# PROC054D_Host_Connector.net
KiCad netlist of a schematic drawn in Altium Designer
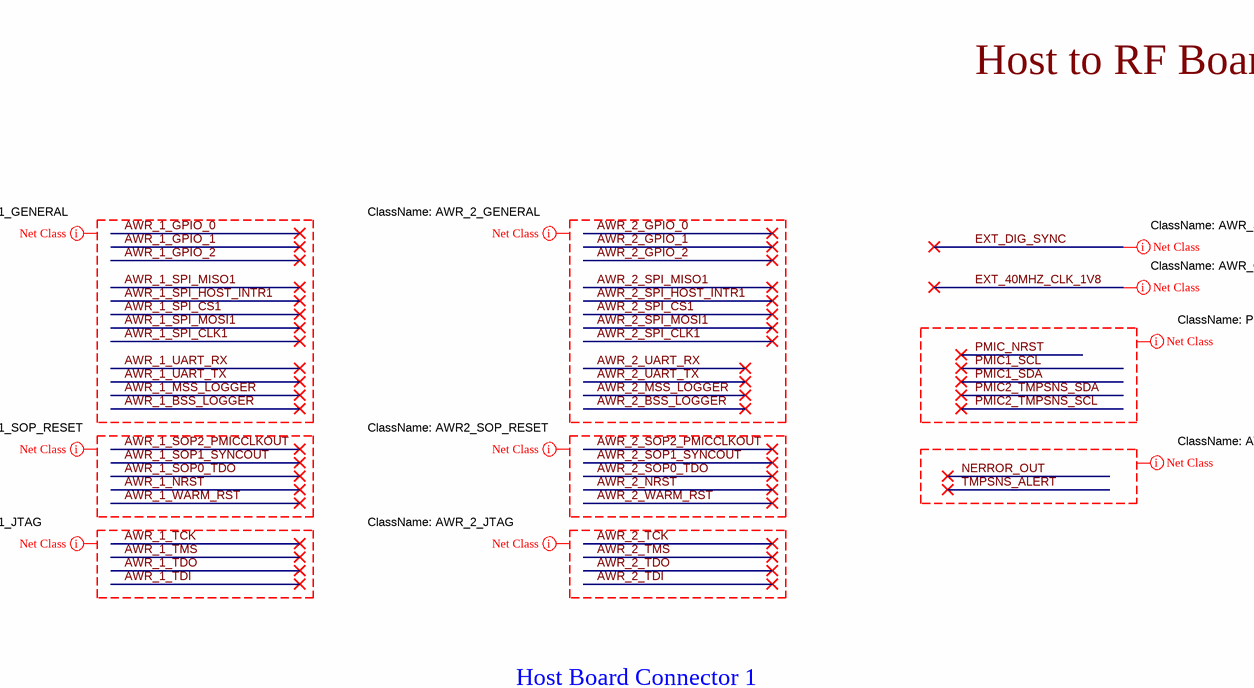
[diagram p0: PROC054D_Host_Connector.SchDoc, top left]
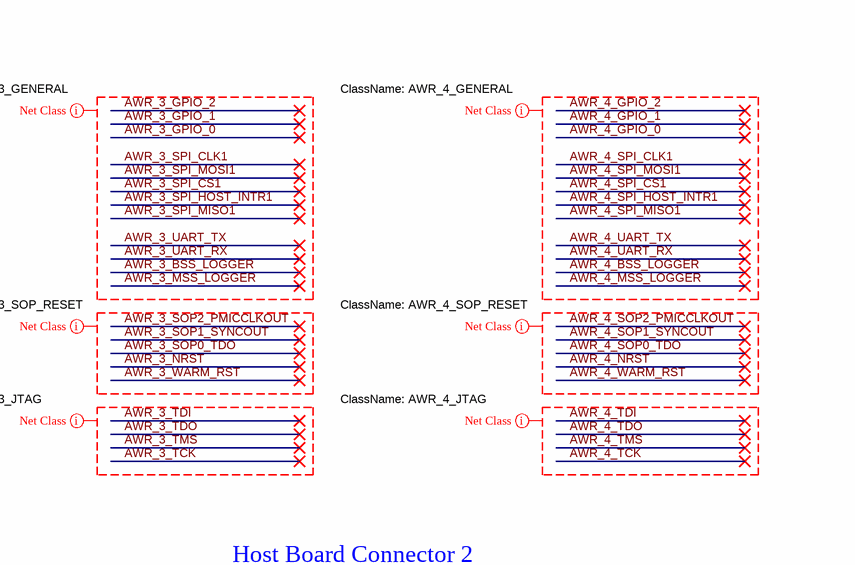
[diagram p1: PROC054D_Host_Connector.SchDoc, top right]
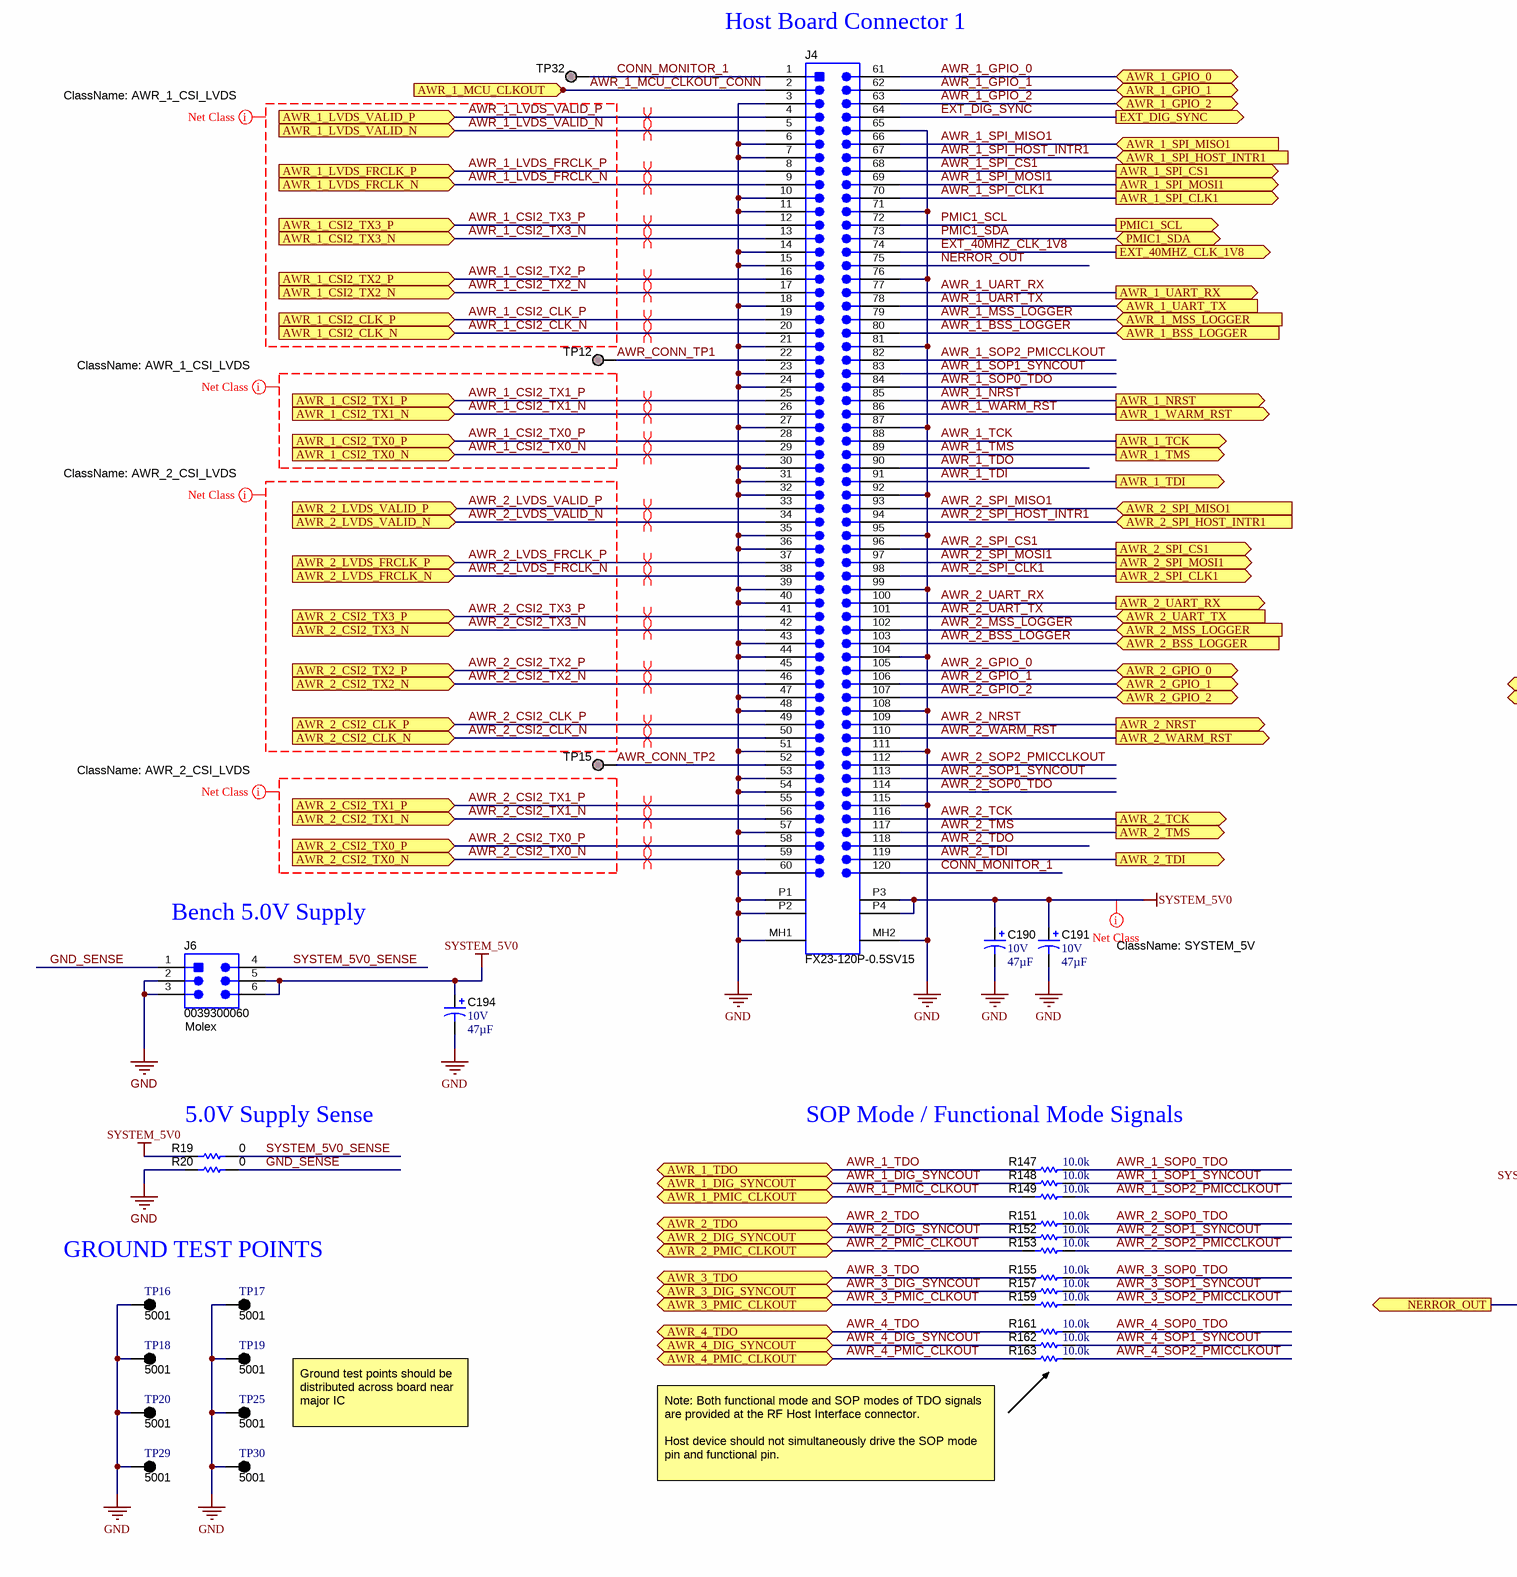
[diagram p2: PROC054D_Host_Connector.SchDoc, bottom left]
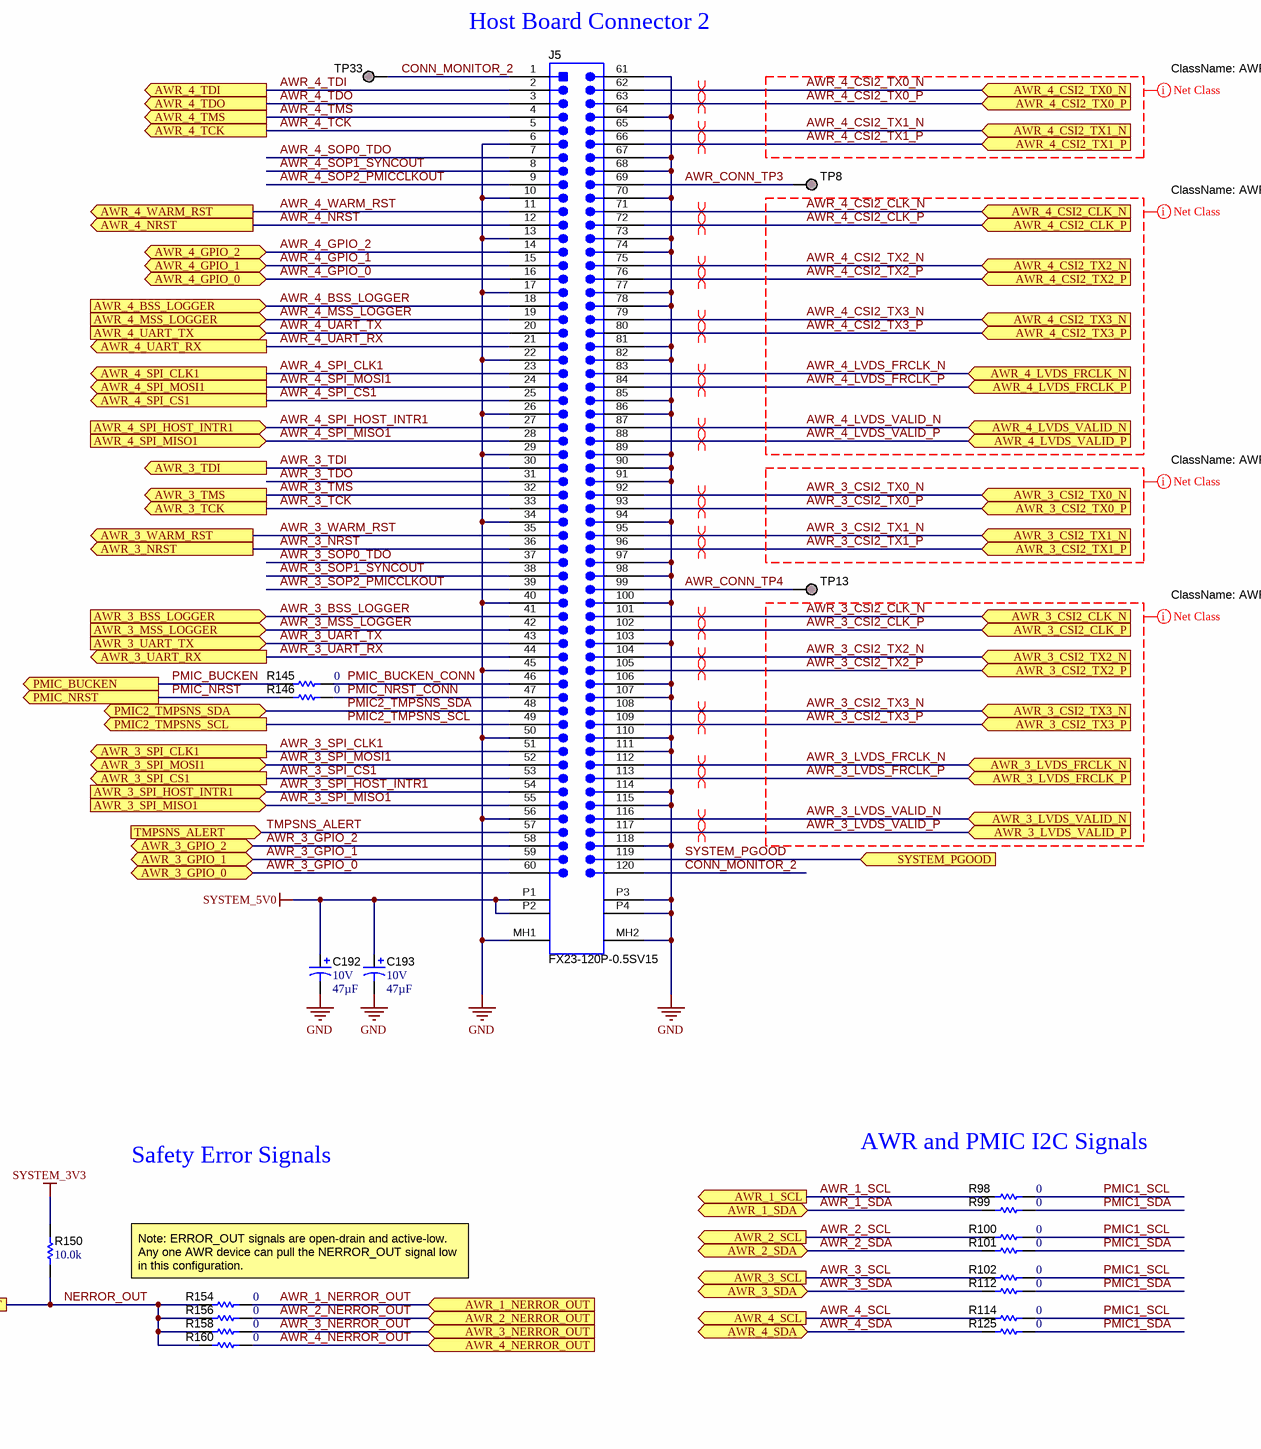
[diagram p3: PROC054D_Host_Connector.SchDoc, bottom right]

(export (version "E")
  (design (tool "Eeschema 10.0.6"))
  (components
    (comp (ref "C190")
      (value "T491B476K010AT")
      (footprint "3528-21")
      (description "CAP, TA, 47 µF, 10 V, +/- 10%, SMD")
      (fields
        (field (name "MANUFACTURER") "Kemet")
        (field (name "VDC_V") "10V")
        (field (name "VALUEDISPLAYED") "47µF")
      )
      (libsource (lib "Altium Vault - TI") (part "CMP-0078216-1"))
    )
    (comp (ref "C191")
      (value "T491B476K010AT")
      (footprint "3528-21")
      (description "CAP, TA, 47 µF, 10 V, +/- 10%, SMD")
      (fields
        (field (name "MANUFACTURER") "Kemet")
        (field (name "VDC_V") "10V")
        (field (name "VALUEDISPLAYED") "47µF")
      )
      (libsource (lib "Altium Vault - TI") (part "Cap_Polarized"))
    )
    (comp (ref "C192")
      (value "T491B476K010AT")
      (footprint "3528-21")
      (description "CAP, TA, 47 µF, 10 V, +/- 10%, SMD")
      (fields
        (field (name "MANUFACTURER") "Kemet")
        (field (name "VDC_V") "10V")
        (field (name "VALUEDISPLAYED") "47µF")
      )
      (libsource (lib "Altium Vault - TI") (part "Cap_Polarized"))
    )
    (comp (ref "C193")
      (value "T491B476K010AT")
      (footprint "3528-21")
      (description "CAP, TA, 47 µF, 10 V, +/- 10%, SMD")
      (fields
        (field (name "MANUFACTURER") "Kemet")
        (field (name "VDC_V") "10V")
        (field (name "VALUEDISPLAYED") "47µF")
      )
      (libsource (lib "Altium Vault - TI") (part "Cap_Polarized"))
    )
    (comp (ref "C194")
      (value "T491B476K010AT")
      (footprint "3528-21")
      (description "CAP, TA, 47 µF, 10 V, +/- 10%, SMD")
      (fields
        (field (name "MANUFACTURER") "Kemet")
        (field (name "VDC_V") "10V")
        (field (name "VALUEDISPLAYED") "47µF")
      )
      (libsource (lib "Altium Vault - TI") (part "CMP-0078216-1"))
    )
    (comp (ref "J4")
      (value "FX23-120P-0.5SV15")
      (footprint "Hirose_FX23-120P-0_5SV15")
      (description "Header(shrouded), 0.5mm, 60x2, Gold, SMT")
      (fields (field (name "MANUFACTURER") "Hirose Electric Co. Ltd."))
      (libsource (lib "Altium Vault - TI") (part "Hirose_FX23-120P-0_5SV15"))
    )
    (comp (ref "J5")
      (value "FX23-120P-0.5SV15")
      (footprint "Hirose_FX23-120P-0_5SV15")
      (description "Header(shrouded), 0.5mm, 60x2, Gold, SMT")
      (fields (field (name "MANUFACTURER") "Hirose Electric Co. Ltd."))
      (libsource (lib "Altium Vault - TI") (part "Hirose_FX23-120P-0_5SV15"))
    )
    (comp (ref "J6")
      (value "0039300060")
      (footprint "Molex_0039300060")
      (description "Header(shrouded), 4.2mm, 3x2, Tin, R/A, TH")
      (fields (field (name "MANUFACTURER") "Molex"))
      (libsource (lib "Altium Vault - TI") (part "CMP-0082107-1"))
    )
    (comp (ref "R19")
      (value "PMR10EZPJ000")
      (footprint "0805L")
      (description "RES, 0, 0%,  W, AEC-Q200 Grade 0, 0805")
      (fields (field (name "MANUFACTURER") "Rohm") (field (name "VALUEDISPLAYED") "0"))
      (libsource (lib "Altium Vault - TI") (part "CMP-0081857-1"))
    )
    (comp (ref "R20")
      (value "PMR10EZPJ000")
      (footprint "0805L")
      (description "RES, 0, 0%,  W, AEC-Q200 Grade 0, 0805")
      (fields (field (name "MANUFACTURER") "Rohm") (field (name "VALUEDISPLAYED") "0"))
      (libsource (lib "Altium Vault - TI") (part "CMP-0081857-1"))
    )
    (comp (ref "R98")
      (value "CRCW04020000Z0EDHP")
      (footprint "0402S")
      (description "RES, 0, 0%, 0.2 W, AEC-Q200 Grade 0, 0402")
      (fields (field (name "MANUFACTURER") "Vishay-Dale") (field (name "VALUEDISPLAYED") "0"))
      (libsource (lib "Altium Vault - TI") (part "CMP-0081856-1"))
    )
    (comp (ref "R99")
      (value "CRCW04020000Z0EDHP")
      (footprint "0402S")
      (description "RES, 0, 0%, 0.2 W, AEC-Q200 Grade 0, 0402")
      (fields (field (name "MANUFACTURER") "Vishay-Dale") (field (name "VALUEDISPLAYED") "0"))
      (libsource (lib "Altium Vault - TI") (part "CMP-0081856-1"))
    )
    (comp (ref "R100")
      (value "CRCW04020000Z0EDHP")
      (footprint "0402S")
      (description "RES, 0, 0%, 0.2 W, AEC-Q200 Grade 0, 0402")
      (fields (field (name "MANUFACTURER") "Vishay-Dale") (field (name "VALUEDISPLAYED") "0"))
      (libsource (lib "Altium Vault - TI") (part "CMP-0081856-1"))
    )
    (comp (ref "R101")
      (value "CRCW04020000Z0EDHP")
      (footprint "0402S")
      (description "RES, 0, 0%, 0.2 W, AEC-Q200 Grade 0, 0402")
      (fields (field (name "MANUFACTURER") "Vishay-Dale") (field (name "VALUEDISPLAYED") "0"))
      (libsource (lib "Altium Vault - TI") (part "CMP-0081856-1"))
    )
    (comp (ref "R102")
      (value "CRCW04020000Z0EDHP")
      (footprint "0402S")
      (description "RES, 0, 0%, 0.2 W, AEC-Q200 Grade 0, 0402")
      (fields (field (name "MANUFACTURER") "Vishay-Dale") (field (name "VALUEDISPLAYED") "0"))
      (libsource (lib "Altium Vault - TI") (part "CMP-0081856-1"))
    )
    (comp (ref "R112")
      (value "CRCW04020000Z0EDHP")
      (footprint "0402S")
      (description "RES, 0, 0%, 0.2 W, AEC-Q200 Grade 0, 0402")
      (fields (field (name "MANUFACTURER") "Vishay-Dale") (field (name "VALUEDISPLAYED") "0"))
      (libsource (lib "Altium Vault - TI") (part "CMP-0081856-1"))
    )
    (comp (ref "R114")
      (value "CRCW04020000Z0EDHP")
      (footprint "0402S")
      (description "RES, 0, 0%, 0.2 W, AEC-Q200 Grade 0, 0402")
      (fields (field (name "MANUFACTURER") "Vishay-Dale") (field (name "VALUEDISPLAYED") "0"))
      (libsource (lib "Altium Vault - TI") (part "CMP-0081856-1"))
    )
    (comp (ref "R125")
      (value "CRCW04020000Z0EDHP")
      (footprint "0402S")
      (description "RES, 0, 0%, 0.2 W, AEC-Q200 Grade 0, 0402")
      (fields (field (name "MANUFACTURER") "Vishay-Dale") (field (name "VALUEDISPLAYED") "0"))
      (libsource (lib "Altium Vault - TI") (part "CMP-0081856-1"))
    )
    (comp (ref "R145")
      (value "ERJ-2GE0R00X")
      (footprint "0402")
      (description "RES, 0, 5%, 0.1 W, AEC-Q200 Grade 0, 0402")
      (fields (field (name "MANUFACTURER") "Panasonic") (field (name "VALUEDISPLAYED") "0"))
      (libsource (lib "Altium Vault - TI") (part "Resistor"))
    )
    (comp (ref "R146")
      (value "ERJ-2GE0R00X")
      (footprint "0402")
      (description "RES, 0, 5%, 0.1 W, AEC-Q200 Grade 0, 0402")
      (fields (field (name "MANUFACTURER") "Panasonic") (field (name "VALUEDISPLAYED") "0"))
      (libsource (lib "Altium Vault - TI") (part "Resistor"))
    )
    (comp (ref "R147")
      (value "CRCW040210K0FKED")
      (footprint "0402")
      (description "RES, 10.0 k, 1%, 0.063 W, AEC-Q200 Grade 0, 0402")
      (fields (field (name "MANUFACTURER") "Vishay-Dale") (field (name "VALUEDISPLAYED") "10.0k"))
      (libsource (lib "Altium Vault - TI") (part "Resistor"))
    )
    (comp (ref "R148")
      (value "CRCW040210K0FKED")
      (footprint "0402")
      (description "RES, 10.0 k, 1%, 0.063 W, AEC-Q200 Grade 0, 0402")
      (fields (field (name "MANUFACTURER") "Vishay-Dale") (field (name "VALUEDISPLAYED") "10.0k"))
      (libsource (lib "Altium Vault - TI") (part "Resistor"))
    )
    (comp (ref "R149")
      (value "CRCW040210K0FKED")
      (footprint "0402")
      (description "RES, 10.0 k, 1%, 0.063 W, AEC-Q200 Grade 0, 0402")
      (fields (field (name "MANUFACTURER") "Vishay-Dale") (field (name "VALUEDISPLAYED") "10.0k"))
      (libsource (lib "Altium Vault - TI") (part "Resistor"))
    )
    (comp (ref "R150")
      (value "CRCW040210K0FKED")
      (footprint "0402")
      (description "RES, 10.0 k, 1%, 0.063 W, AEC-Q200 Grade 0, 0402")
      (fields (field (name "MANUFACTURER") "Vishay-Dale") (field (name "VALUEDISPLAYED") "10.0k"))
      (libsource (lib "Altium Vault - TI") (part "Resistor"))
    )
    (comp (ref "R151")
      (value "CRCW040210K0FKED")
      (footprint "0402")
      (description "RES, 10.0 k, 1%, 0.063 W, AEC-Q200 Grade 0, 0402")
      (fields (field (name "MANUFACTURER") "Vishay-Dale") (field (name "VALUEDISPLAYED") "10.0k"))
      (libsource (lib "Altium Vault - TI") (part "Resistor"))
    )
    (comp (ref "R152")
      (value "CRCW040210K0FKED")
      (footprint "0402")
      (description "RES, 10.0 k, 1%, 0.063 W, AEC-Q200 Grade 0, 0402")
      (fields (field (name "MANUFACTURER") "Vishay-Dale") (field (name "VALUEDISPLAYED") "10.0k"))
      (libsource (lib "Altium Vault - TI") (part "Resistor"))
    )
    (comp (ref "R153")
      (value "CRCW040210K0FKED")
      (footprint "0402")
      (description "RES, 10.0 k, 1%, 0.063 W, AEC-Q200 Grade 0, 0402")
      (fields (field (name "MANUFACTURER") "Vishay-Dale") (field (name "VALUEDISPLAYED") "10.0k"))
      (libsource (lib "Altium Vault - TI") (part "Resistor"))
    )
    (comp (ref "R154")
      (value "CRCW04020000Z0EDHP")
      (footprint "0402S")
      (description "RES, 0, 0%, 0.2 W, AEC-Q200 Grade 0, 0402")
      (fields (field (name "MANUFACTURER") "Vishay-Dale") (field (name "VALUEDISPLAYED") "0"))
      (libsource (lib "Altium Vault - TI") (part "CMP-0081856-1"))
    )
    (comp (ref "R155")
      (value "CRCW040210K0FKED")
      (footprint "0402")
      (description "RES, 10.0 k, 1%, 0.063 W, AEC-Q200 Grade 0, 0402")
      (fields (field (name "MANUFACTURER") "Vishay-Dale") (field (name "VALUEDISPLAYED") "10.0k"))
      (libsource (lib "Altium Vault - TI") (part "Resistor"))
    )
    (comp (ref "R156")
      (value "CRCW04020000Z0EDHP")
      (footprint "0402S")
      (description "RES, 0, 0%, 0.2 W, AEC-Q200 Grade 0, 0402")
      (fields (field (name "MANUFACTURER") "Vishay-Dale") (field (name "VALUEDISPLAYED") "0"))
      (libsource (lib "Altium Vault - TI") (part "CMP-0081856-1"))
    )
    (comp (ref "R157")
      (value "CRCW040210K0FKED")
      (footprint "0402")
      (description "RES, 10.0 k, 1%, 0.063 W, AEC-Q200 Grade 0, 0402")
      (fields (field (name "MANUFACTURER") "Vishay-Dale") (field (name "VALUEDISPLAYED") "10.0k"))
      (libsource (lib "Altium Vault - TI") (part "Resistor"))
    )
    (comp (ref "R158")
      (value "CRCW04020000Z0EDHP")
      (footprint "0402S")
      (description "RES, 0, 0%, 0.2 W, AEC-Q200 Grade 0, 0402")
      (fields (field (name "MANUFACTURER") "Vishay-Dale") (field (name "VALUEDISPLAYED") "0"))
      (libsource (lib "Altium Vault - TI") (part "CMP-0081856-1"))
    )
    (comp (ref "R159")
      (value "CRCW040210K0FKED")
      (footprint "0402")
      (description "RES, 10.0 k, 1%, 0.063 W, AEC-Q200 Grade 0, 0402")
      (fields (field (name "MANUFACTURER") "Vishay-Dale") (field (name "VALUEDISPLAYED") "10.0k"))
      (libsource (lib "Altium Vault - TI") (part "Resistor"))
    )
    (comp (ref "R160")
      (value "CRCW04020000Z0EDHP")
      (footprint "0402S")
      (description "RES, 0, 0%, 0.2 W, AEC-Q200 Grade 0, 0402")
      (fields (field (name "MANUFACTURER") "Vishay-Dale") (field (name "VALUEDISPLAYED") "0"))
      (libsource (lib "Altium Vault - TI") (part "CMP-0081856-1"))
    )
    (comp (ref "R161")
      (value "CRCW040210K0FKED")
      (footprint "0402")
      (description "RES, 10.0 k, 1%, 0.063 W, AEC-Q200 Grade 0, 0402")
      (fields (field (name "MANUFACTURER") "Vishay-Dale") (field (name "VALUEDISPLAYED") "10.0k"))
      (libsource (lib "Altium Vault - TI") (part "Resistor"))
    )
    (comp (ref "R162")
      (value "CRCW040210K0FKED")
      (footprint "0402")
      (description "RES, 10.0 k, 1%, 0.063 W, AEC-Q200 Grade 0, 0402")
      (fields (field (name "MANUFACTURER") "Vishay-Dale") (field (name "VALUEDISPLAYED") "10.0k"))
      (libsource (lib "Altium Vault - TI") (part "Resistor"))
    )
    (comp (ref "R163")
      (value "CRCW040210K0FKED")
      (footprint "0402")
      (description "RES, 10.0 k, 1%, 0.063 W, AEC-Q200 Grade 0, 0402")
      (fields (field (name "MANUFACTURER") "Vishay-Dale") (field (name "VALUEDISPLAYED") "10.0k"))
      (libsource (lib "Altium Vault - TI") (part "Resistor"))
    )
    (comp (ref "TP8")
      (value "TP_SM_1MM")
      (footprint "TP_SM_1MM")
      (description "1mm Test Point, SMT")
      (fields (field (name "MANUFACTURER") "Any") (field (name "PUBLISHER") "Texas Instruments"))
      (libsource (lib "Altium Vault - TI") (part "CMP-0003825-1"))
    )
    (comp (ref "TP12")
      (value "TP_SM_1MM")
      (footprint "TP_SM_1MM")
      (description "1mm Test Point, SMT")
      (fields (field (name "MANUFACTURER") "Any") (field (name "PUBLISHER") "Texas Instruments"))
      (libsource (lib "Altium Vault - TI") (part "CMP-0003825-1"))
    )
    (comp (ref "TP13")
      (value "TP_SM_1MM")
      (footprint "TP_SM_1MM")
      (description "1mm Test Point, SMT")
      (fields (field (name "MANUFACTURER") "Any") (field (name "PUBLISHER") "Texas Instruments"))
      (libsource (lib "Altium Vault - TI") (part "CMP-0003825-1"))
    )
    (comp (ref "TP15")
      (value "TP_SM_1MM")
      (footprint "TP_SM_1MM")
      (description "1mm Test Point, SMT")
      (fields (field (name "MANUFACTURER") "Any") (field (name "PUBLISHER") "Texas Instruments"))
      (libsource (lib "Altium Vault - TI") (part "CMP-0003825-1"))
    )
    (comp (ref "TP16")
      (value "5001")
      (footprint "Keystone5001")
      (description "Test Point, Miniature, Black, TH")
      (fields (field (name "MANUFACTURER") "Keystone") (field (name "PUBLISHER") "Texas Instruments"))
      (libsource (lib "Altium Vault - TI") (part "5001"))
    )
    (comp (ref "TP17")
      (value "5001")
      (footprint "Keystone5001")
      (description "Test Point, Miniature, Black, TH")
      (fields (field (name "MANUFACTURER") "Keystone") (field (name "PUBLISHER") "Texas Instruments"))
      (libsource (lib "Altium Vault - TI") (part "5001"))
    )
    (comp (ref "TP18")
      (value "5001")
      (footprint "Keystone5001")
      (description "Test Point, Miniature, Black, TH")
      (fields (field (name "MANUFACTURER") "Keystone") (field (name "PUBLISHER") "Texas Instruments"))
      (libsource (lib "Altium Vault - TI") (part "5001"))
    )
    (comp (ref "TP19")
      (value "5001")
      (footprint "Keystone5001")
      (description "Test Point, Miniature, Black, TH")
      (fields (field (name "MANUFACTURER") "Keystone") (field (name "PUBLISHER") "Texas Instruments"))
      (libsource (lib "Altium Vault - TI") (part "5001"))
    )
    (comp (ref "TP20")
      (value "5001")
      (footprint "Keystone5001")
      (description "Test Point, Miniature, Black, TH")
      (fields (field (name "MANUFACTURER") "Keystone") (field (name "PUBLISHER") "Texas Instruments"))
      (libsource (lib "Altium Vault - TI") (part "5001"))
    )
    (comp (ref "TP25")
      (value "5001")
      (footprint "Keystone5001")
      (description "Test Point, Miniature, Black, TH")
      (fields (field (name "MANUFACTURER") "Keystone") (field (name "PUBLISHER") "Texas Instruments"))
      (libsource (lib "Altium Vault - TI") (part "5001"))
    )
    (comp (ref "TP29")
      (value "5001")
      (footprint "Keystone5001")
      (description "Test Point, Miniature, Black, TH")
      (fields (field (name "MANUFACTURER") "Keystone") (field (name "PUBLISHER") "Texas Instruments"))
      (libsource (lib "Altium Vault - TI") (part "5001"))
    )
    (comp (ref "TP30")
      (value "5001")
      (footprint "Keystone5001")
      (description "Test Point, Miniature, Black, TH")
      (fields (field (name "MANUFACTURER") "Keystone") (field (name "PUBLISHER") "Texas Instruments"))
      (libsource (lib "Altium Vault - TI") (part "5001"))
    )
    (comp (ref "TP32")
      (value "TP_SM_1MM")
      (footprint "TP_SM_1MM")
      (description "1mm Test Point, SMT")
      (fields (field (name "MANUFACTURER") "Any") (field (name "PUBLISHER") "Texas Instruments"))
      (libsource (lib "Altium Vault - TI") (part "CMP-0003825-1"))
    )
    (comp (ref "TP33")
      (value "TP_SM_1MM")
      (footprint "TP_SM_1MM")
      (description "1mm Test Point, SMT")
      (fields (field (name "MANUFACTURER") "Any") (field (name "PUBLISHER") "Texas Instruments"))
      (libsource (lib "Altium Vault - TI") (part "CMP-0003825-1"))
    )
  )
  (nets
    (net (code "1") (name "/AWR_1_BSS_LOGGER") (class "Default")
      (node (ref "J4") (pin "80") (pinfunction "80_80") (pintype "passive+no_connect"))
    )
    (net (code "2") (name "/AWR_1_CSI2_CLK_N") (class "Default")
      (node (ref "J4") (pin "20") (pinfunction "20_20") (pintype "passive"))
    )
    (net (code "3") (name "/AWR_1_CSI2_CLK_P") (class "Default")
      (node (ref "J4") (pin "19") (pinfunction "19_19") (pintype "passive"))
    )
    (net (code "4") (name "/AWR_1_CSI2_TX0_N") (class "Default")
      (node (ref "J4") (pin "29") (pinfunction "29_29") (pintype "passive"))
    )
    (net (code "5") (name "/AWR_1_CSI2_TX0_P") (class "Default")
      (node (ref "J4") (pin "28") (pinfunction "28_28") (pintype "passive"))
    )
    (net (code "6") (name "/AWR_1_CSI2_TX1_N") (class "Default")
      (node (ref "J4") (pin "26") (pinfunction "26_26") (pintype "passive"))
    )
    (net (code "7") (name "/AWR_1_CSI2_TX1_P") (class "Default")
      (node (ref "J4") (pin "25") (pinfunction "25_25") (pintype "passive"))
    )
    (net (code "8") (name "/AWR_1_CSI2_TX2_N") (class "Default")
      (node (ref "J4") (pin "17") (pinfunction "17_17") (pintype "passive"))
    )
    (net (code "9") (name "/AWR_1_CSI2_TX2_P") (class "Default")
      (node (ref "J4") (pin "16") (pinfunction "16_16") (pintype "passive"))
    )
    (net (code "10") (name "/AWR_1_CSI2_TX3_N") (class "Default")
      (node (ref "J4") (pin "13") (pinfunction "13_13") (pintype "passive"))
    )
    (net (code "11") (name "/AWR_1_CSI2_TX3_P") (class "Default")
      (node (ref "J4") (pin "12") (pinfunction "12_12") (pintype "passive"))
    )
    (net (code "12") (name "/AWR_1_DIG_SYNCOUT") (class "Default")
      (node (ref "R148") (pin "1") (pinfunction "1_1") (pintype "passive"))
    )
    (net (code "13") (name "/AWR_1_GPIO_0") (class "Default")
      (node (ref "J4") (pin "61") (pinfunction "61_61") (pintype "passive"))
    )
    (net (code "14") (name "/AWR_1_GPIO_1") (class "Default")
      (node (ref "J4") (pin "62") (pinfunction "62_62") (pintype "passive"))
    )
    (net (code "15") (name "/AWR_1_GPIO_2") (class "Default")
      (node (ref "J4") (pin "63") (pinfunction "63_63") (pintype "passive"))
    )
    (net (code "16") (name "/AWR_1_LVDS_FRCLK_N") (class "Default")
      (node (ref "J4") (pin "9") (pinfunction "9_9") (pintype "passive"))
    )
    (net (code "17") (name "/AWR_1_LVDS_FRCLK_P") (class "Default")
      (node (ref "J4") (pin "8") (pinfunction "8_8") (pintype "passive"))
    )
    (net (code "18") (name "/AWR_1_LVDS_VALID_N") (class "Default")
      (node (ref "J4") (pin "5") (pinfunction "5_5") (pintype "passive"))
    )
    (net (code "19") (name "/AWR_1_LVDS_VALID_P") (class "Default")
      (node (ref "J4") (pin "4") (pinfunction "4_4") (pintype "passive"))
    )
    (net (code "20") (name "/AWR_1_MCU_CLKOUT_CONN") (class "Default")
      (node (ref "J4") (pin "2") (pinfunction "2_2") (pintype "passive"))
    )
    (net (code "21") (name "/AWR_1_MSS_LOGGER") (class "Default")
      (node (ref "J4") (pin "79") (pinfunction "79_79") (pintype "passive+no_connect"))
    )
    (net (code "22") (name "/AWR_1_NERROR_OUT") (class "Default")
      (node (ref "R154") (pin "1") (pinfunction "1_1") (pintype "passive"))
    )
    (net (code "23") (name "/AWR_1_NRST") (class "Default")
      (node (ref "J4") (pin "85") (pinfunction "85_85") (pintype "passive+no_connect"))
    )
    (net (code "24") (name "/AWR_1_PMIC_CLKOUT") (class "Default")
      (node (ref "R149") (pin "1") (pinfunction "1_1") (pintype "passive"))
    )
    (net (code "25") (name "/AWR_1_SCL") (class "Default")
      (node (ref "R98") (pin "2") (pinfunction "2_2") (pintype "passive"))
    )
    (net (code "26") (name "/AWR_1_SDA") (class "Default")
      (node (ref "R99") (pin "2") (pinfunction "2_2") (pintype "passive"))
    )
    (net (code "27") (name "/AWR_1_SOP0_TDO") (class "Default")
      (node (ref "J4") (pin "84") (pinfunction "84_84") (pintype "passive"))
      (node (ref "R147") (pin "2") (pinfunction "2_2") (pintype "passive"))
    )
    (net (code "28") (name "/AWR_1_SOP1_SYNCOUT") (class "Default")
      (node (ref "J4") (pin "83") (pinfunction "83_83") (pintype "passive"))
      (node (ref "R148") (pin "2") (pinfunction "2_2") (pintype "passive"))
    )
    (net (code "29") (name "/AWR_1_SOP2_PMICCLKOUT") (class "Default")
      (node (ref "J4") (pin "82") (pinfunction "82_82") (pintype "passive"))
      (node (ref "R149") (pin "2") (pinfunction "2_2") (pintype "passive"))
    )
    (net (code "30") (name "/AWR_1_SPI_CLK1") (class "Default")
      (node (ref "J4") (pin "70") (pinfunction "70_70") (pintype "passive"))
    )
    (net (code "31") (name "/AWR_1_SPI_CS1") (class "Default")
      (node (ref "J4") (pin "68") (pinfunction "68_68") (pintype "passive"))
    )
    (net (code "32") (name "/AWR_1_SPI_HOST_INTR1") (class "Default")
      (node (ref "J4") (pin "67") (pinfunction "67_67") (pintype "passive"))
    )
    (net (code "33") (name "/AWR_1_SPI_MISO1") (class "Default")
      (node (ref "J4") (pin "66") (pinfunction "66_66") (pintype "passive"))
    )
    (net (code "34") (name "/AWR_1_SPI_MOSI1") (class "Default")
      (node (ref "J4") (pin "69") (pinfunction "69_69") (pintype "passive"))
    )
    (net (code "35") (name "/AWR_1_TCK") (class "Default")
      (node (ref "J4") (pin "88") (pinfunction "88_88") (pintype "passive+no_connect"))
    )
    (net (code "36") (name "/AWR_1_TDI") (class "Default")
      (node (ref "J4") (pin "91") (pinfunction "91_91") (pintype "passive+no_connect"))
    )
    (net (code "37") (name "/AWR_1_TDO") (class "Default")
      (node (ref "J4") (pin "90") (pinfunction "90_90") (pintype "passive"))
      (node (ref "R147") (pin "1") (pinfunction "1_1") (pintype "passive"))
    )
    (net (code "38") (name "/AWR_1_TMS") (class "Default")
      (node (ref "J4") (pin "89") (pinfunction "89_89") (pintype "passive+no_connect"))
    )
    (net (code "39") (name "/AWR_1_UART_RX") (class "Default")
      (node (ref "J4") (pin "77") (pinfunction "77_77") (pintype "passive+no_connect"))
    )
    (net (code "40") (name "/AWR_1_UART_TX") (class "Default")
      (node (ref "J4") (pin "78") (pinfunction "78_78") (pintype "passive+no_connect"))
    )
    (net (code "41") (name "/AWR_1_WARM_RST") (class "Default")
      (node (ref "J4") (pin "86") (pinfunction "86_86") (pintype "passive+no_connect"))
    )
    (net (code "42") (name "/AWR_2_BSS_LOGGER") (class "Default")
      (node (ref "J4") (pin "103") (pinfunction "103_103") (pintype "passive"))
    )
    (net (code "43") (name "/AWR_2_CSI2_CLK_N") (class "Default")
      (node (ref "J4") (pin "50") (pinfunction "50_50") (pintype "passive"))
    )
    (net (code "44") (name "/AWR_2_CSI2_CLK_P") (class "Default")
      (node (ref "J4") (pin "49") (pinfunction "49_49") (pintype "passive"))
    )
    (net (code "45") (name "/AWR_2_CSI2_TX0_N") (class "Default")
      (node (ref "J4") (pin "59") (pinfunction "59_59") (pintype "passive"))
    )
    (net (code "46") (name "/AWR_2_CSI2_TX0_P") (class "Default")
      (node (ref "J4") (pin "58") (pinfunction "58_58") (pintype "passive"))
    )
    (net (code "47") (name "/AWR_2_CSI2_TX1_N") (class "Default")
      (node (ref "J4") (pin "56") (pinfunction "56_56") (pintype "passive"))
    )
    (net (code "48") (name "/AWR_2_CSI2_TX1_P") (class "Default")
      (node (ref "J4") (pin "55") (pinfunction "55_55") (pintype "passive"))
    )
    (net (code "49") (name "/AWR_2_CSI2_TX2_N") (class "Default")
      (node (ref "J4") (pin "46") (pinfunction "46_46") (pintype "passive"))
    )
    (net (code "50") (name "/AWR_2_CSI2_TX2_P") (class "Default")
      (node (ref "J4") (pin "45") (pinfunction "45_45") (pintype "passive"))
    )
    (net (code "51") (name "/AWR_2_CSI2_TX3_N") (class "Default")
      (node (ref "J4") (pin "42") (pinfunction "42_42") (pintype "passive"))
    )
    (net (code "52") (name "/AWR_2_CSI2_TX3_P") (class "Default")
      (node (ref "J4") (pin "41") (pinfunction "41_41") (pintype "passive"))
    )
    (net (code "53") (name "/AWR_2_DIG_SYNCOUT") (class "Default")
      (node (ref "R152") (pin "1") (pinfunction "1_1") (pintype "passive"))
    )
    (net (code "54") (name "/AWR_2_GPIO_0") (class "Default")
      (node (ref "J4") (pin "105") (pinfunction "105_105") (pintype "passive"))
    )
    (net (code "55") (name "/AWR_2_GPIO_1") (class "Default")
      (node (ref "J4") (pin "106") (pinfunction "106_106") (pintype "passive"))
    )
    (net (code "56") (name "/AWR_2_GPIO_2") (class "Default")
      (node (ref "J4") (pin "107") (pinfunction "107_107") (pintype "passive"))
    )
    (net (code "57") (name "/AWR_2_LVDS_FRCLK_N") (class "Default")
      (node (ref "J4") (pin "38") (pinfunction "38_38") (pintype "passive"))
    )
    (net (code "58") (name "/AWR_2_LVDS_FRCLK_P") (class "Default")
      (node (ref "J4") (pin "37") (pinfunction "37_37") (pintype "passive"))
    )
    (net (code "59") (name "/AWR_2_LVDS_VALID_N") (class "Default")
      (node (ref "J4") (pin "34") (pinfunction "34_34") (pintype "passive"))
    )
    (net (code "60") (name "/AWR_2_LVDS_VALID_P") (class "Default")
      (node (ref "J4") (pin "33") (pinfunction "33_33") (pintype "passive"))
    )
    (net (code "61") (name "/AWR_2_MSS_LOGGER") (class "Default")
      (node (ref "J4") (pin "102") (pinfunction "102_102") (pintype "passive"))
    )
    (net (code "62") (name "/AWR_2_NERROR_OUT") (class "Default")
      (node (ref "R156") (pin "1") (pinfunction "1_1") (pintype "passive"))
    )
    (net (code "63") (name "/AWR_2_NRST") (class "Default")
      (node (ref "J4") (pin "109") (pinfunction "109_109") (pintype "passive"))
    )
    (net (code "64") (name "/AWR_2_PMIC_CLKOUT") (class "Default")
      (node (ref "R153") (pin "1") (pinfunction "1_1") (pintype "passive"))
    )
    (net (code "65") (name "/AWR_2_SCL") (class "Default")
      (node (ref "R100") (pin "2") (pinfunction "2_2") (pintype "passive"))
    )
    (net (code "66") (name "/AWR_2_SDA") (class "Default")
      (node (ref "R101") (pin "2") (pinfunction "2_2") (pintype "passive"))
    )
    (net (code "67") (name "/AWR_2_SOP0_TDO") (class "Default")
      (node (ref "J4") (pin "114") (pinfunction "114_114") (pintype "passive"))
      (node (ref "R151") (pin "2") (pinfunction "2_2") (pintype "passive"))
    )
    (net (code "68") (name "/AWR_2_SOP1_SYNCOUT") (class "Default")
      (node (ref "J4") (pin "113") (pinfunction "113_113") (pintype "passive"))
      (node (ref "R152") (pin "2") (pinfunction "2_2") (pintype "passive"))
    )
    (net (code "69") (name "/AWR_2_SOP2_PMICCLKOUT") (class "Default")
      (node (ref "J4") (pin "112") (pinfunction "112_112") (pintype "passive"))
      (node (ref "R153") (pin "2") (pinfunction "2_2") (pintype "passive"))
    )
    (net (code "70") (name "/AWR_2_SPI_CLK1") (class "Default")
      (node (ref "J4") (pin "98") (pinfunction "98_98") (pintype "passive"))
    )
    (net (code "71") (name "/AWR_2_SPI_CS1") (class "Default")
      (node (ref "J4") (pin "96") (pinfunction "96_96") (pintype "passive"))
    )
    (net (code "72") (name "/AWR_2_SPI_HOST_INTR1") (class "Default")
      (node (ref "J4") (pin "94") (pinfunction "94_94") (pintype "passive"))
    )
    (net (code "73") (name "/AWR_2_SPI_MISO1") (class "Default")
      (node (ref "J4") (pin "93") (pinfunction "93_93") (pintype "passive"))
    )
    (net (code "74") (name "/AWR_2_SPI_MOSI1") (class "Default")
      (node (ref "J4") (pin "97") (pinfunction "97_97") (pintype "passive"))
    )
    (net (code "75") (name "/AWR_2_TCK") (class "Default")
      (node (ref "J4") (pin "116") (pinfunction "116_116") (pintype "passive"))
    )
    (net (code "76") (name "/AWR_2_TDI") (class "Default")
      (node (ref "J4") (pin "119") (pinfunction "119_119") (pintype "passive"))
    )
    (net (code "77") (name "/AWR_2_TDO") (class "Default")
      (node (ref "J4") (pin "118") (pinfunction "118_118") (pintype "passive"))
      (node (ref "R151") (pin "1") (pinfunction "1_1") (pintype "passive"))
    )
    (net (code "78") (name "/AWR_2_TMS") (class "Default")
      (node (ref "J4") (pin "117") (pinfunction "117_117") (pintype "passive"))
    )
    (net (code "79") (name "/AWR_2_UART_RX") (class "Default")
      (node (ref "J4") (pin "100") (pinfunction "100_100") (pintype "passive"))
    )
    (net (code "80") (name "/AWR_2_UART_TX") (class "Default")
      (node (ref "J4") (pin "101") (pinfunction "101_101") (pintype "passive"))
    )
    (net (code "81") (name "/AWR_2_WARM_RST") (class "Default")
      (node (ref "J4") (pin "110") (pinfunction "110_110") (pintype "passive"))
    )
    (net (code "82") (name "/AWR_3_BSS_LOGGER") (class "Default")
      (node (ref "J5") (pin "41") (pinfunction "41_41") (pintype "passive+no_connect"))
    )
    (net (code "83") (name "/AWR_3_CSI2_CLK_N") (class "Default")
      (node (ref "J5") (pin "101") (pinfunction "101_101") (pintype "passive"))
    )
    (net (code "84") (name "/AWR_3_CSI2_CLK_P") (class "Default")
      (node (ref "J5") (pin "102") (pinfunction "102_102") (pintype "passive"))
    )
    (net (code "85") (name "/AWR_3_CSI2_TX0_N") (class "Default")
      (node (ref "J5") (pin "92") (pinfunction "92_92") (pintype "passive"))
    )
    (net (code "86") (name "/AWR_3_CSI2_TX0_P") (class "Default")
      (node (ref "J5") (pin "93") (pinfunction "93_93") (pintype "passive"))
    )
    (net (code "87") (name "/AWR_3_CSI2_TX1_N") (class "Default")
      (node (ref "J5") (pin "95") (pinfunction "95_95") (pintype "passive"))
    )
    (net (code "88") (name "/AWR_3_CSI2_TX1_P") (class "Default")
      (node (ref "J5") (pin "96") (pinfunction "96_96") (pintype "passive"))
    )
    (net (code "89") (name "/AWR_3_CSI2_TX2_N") (class "Default")
      (node (ref "J5") (pin "104") (pinfunction "104_104") (pintype "passive"))
    )
    (net (code "90") (name "/AWR_3_CSI2_TX2_P") (class "Default")
      (node (ref "J5") (pin "105") (pinfunction "105_105") (pintype "passive"))
    )
    (net (code "91") (name "/AWR_3_CSI2_TX3_N") (class "Default")
      (node (ref "J5") (pin "108") (pinfunction "108_108") (pintype "passive"))
    )
    (net (code "92") (name "/AWR_3_CSI2_TX3_P") (class "Default")
      (node (ref "J5") (pin "109") (pinfunction "109_109") (pintype "passive"))
    )
    (net (code "93") (name "/AWR_3_DIG_SYNCOUT") (class "Default")
      (node (ref "R157") (pin "1") (pinfunction "1_1") (pintype "passive"))
    )
    (net (code "94") (name "/AWR_3_GPIO_0") (class "Default")
      (node (ref "J5") (pin "60") (pinfunction "60_60") (pintype "passive"))
    )
    (net (code "95") (name "/AWR_3_GPIO_1") (class "Default")
      (node (ref "J5") (pin "59") (pinfunction "59_59") (pintype "passive"))
    )
    (net (code "96") (name "/AWR_3_GPIO_2") (class "Default")
      (node (ref "J5") (pin "58") (pinfunction "58_58") (pintype "passive"))
    )
    (net (code "97") (name "/AWR_3_LVDS_FRCLK_N") (class "Default")
      (node (ref "J5") (pin "112") (pinfunction "112_112") (pintype "passive"))
    )
    (net (code "98") (name "/AWR_3_LVDS_FRCLK_P") (class "Default")
      (node (ref "J5") (pin "113") (pinfunction "113_113") (pintype "passive"))
    )
    (net (code "99") (name "/AWR_3_LVDS_VALID_N") (class "Default")
      (node (ref "J5") (pin "116") (pinfunction "116_116") (pintype "passive"))
    )
    (net (code "100") (name "/AWR_3_LVDS_VALID_P") (class "Default")
      (node (ref "J5") (pin "117") (pinfunction "117_117") (pintype "passive"))
    )
    (net (code "101") (name "/AWR_3_MSS_LOGGER") (class "Default")
      (node (ref "J5") (pin "42") (pinfunction "42_42") (pintype "passive+no_connect"))
    )
    (net (code "102") (name "/AWR_3_NERROR_OUT") (class "Default")
      (node (ref "R158") (pin "1") (pinfunction "1_1") (pintype "passive"))
    )
    (net (code "103") (name "/AWR_3_NRST") (class "Default")
      (node (ref "J5") (pin "36") (pinfunction "36_36") (pintype "passive"))
    )
    (net (code "104") (name "/AWR_3_PMIC_CLKOUT") (class "Default")
      (node (ref "R159") (pin "1") (pinfunction "1_1") (pintype "passive"))
    )
    (net (code "105") (name "/AWR_3_SCL") (class "Default")
      (node (ref "R102") (pin "2") (pinfunction "2_2") (pintype "passive"))
    )
    (net (code "106") (name "/AWR_3_SDA") (class "Default")
      (node (ref "R112") (pin "2") (pinfunction "2_2") (pintype "passive"))
    )
    (net (code "107") (name "/AWR_3_SOP0_TDO") (class "Default")
      (node (ref "J5") (pin "37") (pinfunction "37_37") (pintype "passive"))
      (node (ref "R155") (pin "2") (pinfunction "2_2") (pintype "passive"))
    )
    (net (code "108") (name "/AWR_3_SOP1_SYNCOUT") (class "Default")
      (node (ref "J5") (pin "38") (pinfunction "38_38") (pintype "passive"))
      (node (ref "R157") (pin "2") (pinfunction "2_2") (pintype "passive"))
    )
    (net (code "109") (name "/AWR_3_SOP2_PMICCLKOUT") (class "Default")
      (node (ref "J5") (pin "39") (pinfunction "39_39") (pintype "passive"))
      (node (ref "R159") (pin "2") (pinfunction "2_2") (pintype "passive"))
    )
    (net (code "110") (name "/AWR_3_SPI_CLK1") (class "Default")
      (node (ref "J5") (pin "51") (pinfunction "51_51") (pintype "passive+no_connect"))
    )
    (net (code "111") (name "/AWR_3_SPI_CS1") (class "Default")
      (node (ref "J5") (pin "53") (pinfunction "53_53") (pintype "passive+no_connect"))
    )
    (net (code "112") (name "/AWR_3_SPI_HOST_INTR1") (class "Default")
      (node (ref "J5") (pin "54") (pinfunction "54_54") (pintype "passive+no_connect"))
    )
    (net (code "113") (name "/AWR_3_SPI_MISO1") (class "Default")
      (node (ref "J5") (pin "55") (pinfunction "55_55") (pintype "passive+no_connect"))
    )
    (net (code "114") (name "/AWR_3_SPI_MOSI1") (class "Default")
      (node (ref "J5") (pin "52") (pinfunction "52_52") (pintype "passive+no_connect"))
    )
    (net (code "115") (name "/AWR_3_TCK") (class "Default")
      (node (ref "J5") (pin "33") (pinfunction "33_33") (pintype "passive+no_connect"))
    )
    (net (code "116") (name "/AWR_3_TDI") (class "Default")
      (node (ref "J5") (pin "30") (pinfunction "30_30") (pintype "passive+no_connect"))
    )
    (net (code "117") (name "/AWR_3_TDO") (class "Default")
      (node (ref "J5") (pin "31") (pinfunction "31_31") (pintype "passive"))
      (node (ref "R155") (pin "1") (pinfunction "1_1") (pintype "passive"))
    )
    (net (code "118") (name "/AWR_3_TMS") (class "Default")
      (node (ref "J5") (pin "32") (pinfunction "32_32") (pintype "passive+no_connect"))
    )
    (net (code "119") (name "/AWR_3_UART_RX") (class "Default")
      (node (ref "J5") (pin "44") (pinfunction "44_44") (pintype "passive+no_connect"))
    )
    (net (code "120") (name "/AWR_3_UART_TX") (class "Default")
      (node (ref "J5") (pin "43") (pinfunction "43_43") (pintype "passive+no_connect"))
    )
    (net (code "121") (name "/AWR_3_WARM_RST") (class "Default")
      (node (ref "J5") (pin "35") (pinfunction "35_35") (pintype "passive"))
    )
    (net (code "122") (name "/AWR_4_BSS_LOGGER") (class "Default")
      (node (ref "J5") (pin "18") (pinfunction "18_18") (pintype "passive+no_connect"))
    )
    (net (code "123") (name "/AWR_4_CSI2_CLK_N") (class "Default")
      (node (ref "J5") (pin "71") (pinfunction "71_71") (pintype "passive"))
    )
    (net (code "124") (name "/AWR_4_CSI2_CLK_P") (class "Default")
      (node (ref "J5") (pin "72") (pinfunction "72_72") (pintype "passive"))
    )
    (net (code "125") (name "/AWR_4_CSI2_TX0_N") (class "Default")
      (node (ref "J5") (pin "62") (pinfunction "62_62") (pintype "passive"))
    )
    (net (code "126") (name "/AWR_4_CSI2_TX0_P") (class "Default")
      (node (ref "J5") (pin "63") (pinfunction "63_63") (pintype "passive"))
    )
    (net (code "127") (name "/AWR_4_CSI2_TX1_N") (class "Default")
      (node (ref "J5") (pin "65") (pinfunction "65_65") (pintype "passive"))
    )
    (net (code "128") (name "/AWR_4_CSI2_TX1_P") (class "Default")
      (node (ref "J5") (pin "66") (pinfunction "66_66") (pintype "passive"))
    )
    (net (code "129") (name "/AWR_4_CSI2_TX2_N") (class "Default")
      (node (ref "J5") (pin "75") (pinfunction "75_75") (pintype "passive"))
    )
    (net (code "130") (name "/AWR_4_CSI2_TX2_P") (class "Default")
      (node (ref "J5") (pin "76") (pinfunction "76_76") (pintype "passive"))
    )
    (net (code "131") (name "/AWR_4_CSI2_TX3_N") (class "Default")
      (node (ref "J5") (pin "79") (pinfunction "79_79") (pintype "passive"))
    )
    (net (code "132") (name "/AWR_4_CSI2_TX3_P") (class "Default")
      (node (ref "J5") (pin "80") (pinfunction "80_80") (pintype "passive"))
    )
    (net (code "133") (name "/AWR_4_DIG_SYNCOUT") (class "Default")
      (node (ref "R162") (pin "1") (pinfunction "1_1") (pintype "passive"))
    )
    (net (code "134") (name "/AWR_4_GPIO_0") (class "Default")
      (node (ref "J5") (pin "16") (pinfunction "16_16") (pintype "passive+no_connect"))
    )
    (net (code "135") (name "/AWR_4_GPIO_1") (class "Default")
      (node (ref "J5") (pin "15") (pinfunction "15_15") (pintype "passive+no_connect"))
    )
    (net (code "136") (name "/AWR_4_GPIO_2") (class "Default")
      (node (ref "J5") (pin "14") (pinfunction "14_14") (pintype "passive+no_connect"))
    )
    (net (code "137") (name "/AWR_4_LVDS_FRCLK_N") (class "Default")
      (node (ref "J5") (pin "83") (pinfunction "83_83") (pintype "passive"))
    )
    (net (code "138") (name "/AWR_4_LVDS_FRCLK_P") (class "Default")
      (node (ref "J5") (pin "84") (pinfunction "84_84") (pintype "passive"))
    )
    (net (code "139") (name "/AWR_4_LVDS_VALID_N") (class "Default")
      (node (ref "J5") (pin "87") (pinfunction "87_87") (pintype "passive"))
    )
    (net (code "140") (name "/AWR_4_LVDS_VALID_P") (class "Default")
      (node (ref "J5") (pin "88") (pinfunction "88_88") (pintype "passive"))
    )
    (net (code "141") (name "/AWR_4_MSS_LOGGER") (class "Default")
      (node (ref "J5") (pin "19") (pinfunction "19_19") (pintype "passive+no_connect"))
    )
    (net (code "142") (name "/AWR_4_NERROR_OUT") (class "Default")
      (node (ref "R160") (pin "1") (pinfunction "1_1") (pintype "passive"))
    )
    (net (code "143") (name "/AWR_4_NRST") (class "Default")
      (node (ref "J5") (pin "12") (pinfunction "12_12") (pintype "passive+no_connect"))
    )
    (net (code "144") (name "/AWR_4_PMIC_CLKOUT") (class "Default")
      (node (ref "R163") (pin "1") (pinfunction "1_1") (pintype "passive"))
    )
    (net (code "145") (name "/AWR_4_SCL") (class "Default")
      (node (ref "R114") (pin "2") (pinfunction "2_2") (pintype "passive"))
    )
    (net (code "146") (name "/AWR_4_SDA") (class "Default")
      (node (ref "R125") (pin "2") (pinfunction "2_2") (pintype "passive"))
    )
    (net (code "147") (name "/AWR_4_SOP0_TDO") (class "Default")
      (node (ref "J5") (pin "7") (pinfunction "7_7") (pintype "passive"))
      (node (ref "R161") (pin "2") (pinfunction "2_2") (pintype "passive"))
    )
    (net (code "148") (name "/AWR_4_SOP1_SYNCOUT") (class "Default")
      (node (ref "J5") (pin "8") (pinfunction "8_8") (pintype "passive"))
      (node (ref "R162") (pin "2") (pinfunction "2_2") (pintype "passive"))
    )
    (net (code "149") (name "/AWR_4_SOP2_PMICCLKOUT") (class "Default")
      (node (ref "J5") (pin "9") (pinfunction "9_9") (pintype "passive"))
      (node (ref "R163") (pin "2") (pinfunction "2_2") (pintype "passive"))
    )
    (net (code "150") (name "/AWR_4_SPI_CLK1") (class "Default")
      (node (ref "J5") (pin "23") (pinfunction "23_23") (pintype "passive+no_connect"))
    )
    (net (code "151") (name "/AWR_4_SPI_CS1") (class "Default")
      (node (ref "J5") (pin "25") (pinfunction "25_25") (pintype "passive+no_connect"))
    )
    (net (code "152") (name "/AWR_4_SPI_HOST_INTR1") (class "Default")
      (node (ref "J5") (pin "27") (pinfunction "27_27") (pintype "passive+no_connect"))
    )
    (net (code "153") (name "/AWR_4_SPI_MISO1") (class "Default")
      (node (ref "J5") (pin "28") (pinfunction "28_28") (pintype "passive+no_connect"))
    )
    (net (code "154") (name "/AWR_4_SPI_MOSI1") (class "Default")
      (node (ref "J5") (pin "24") (pinfunction "24_24") (pintype "passive+no_connect"))
    )
    (net (code "155") (name "/AWR_4_TCK") (class "Default")
      (node (ref "J5") (pin "5") (pinfunction "5_5") (pintype "passive+no_connect"))
    )
    (net (code "156") (name "/AWR_4_TDI") (class "Default")
      (node (ref "J5") (pin "2") (pinfunction "2_2") (pintype "passive+no_connect"))
    )
    (net (code "157") (name "/AWR_4_TDO") (class "Default")
      (node (ref "J5") (pin "3") (pinfunction "3_3") (pintype "passive"))
      (node (ref "R161") (pin "1") (pinfunction "1_1") (pintype "passive"))
    )
    (net (code "158") (name "/AWR_4_TMS") (class "Default")
      (node (ref "J5") (pin "4") (pinfunction "4_4") (pintype "passive+no_connect"))
    )
    (net (code "159") (name "/AWR_4_UART_RX") (class "Default")
      (node (ref "J5") (pin "21") (pinfunction "21_21") (pintype "passive+no_connect"))
    )
    (net (code "160") (name "/AWR_4_UART_TX") (class "Default")
      (node (ref "J5") (pin "20") (pinfunction "20_20") (pintype "passive+no_connect"))
    )
    (net (code "161") (name "/AWR_4_WARM_RST") (class "Default")
      (node (ref "J5") (pin "11") (pinfunction "11_11") (pintype "passive+no_connect"))
    )
    (net (code "162") (name "/AWR_CONN_TP1") (class "Default")
      (node (ref "J4") (pin "22") (pinfunction "22_22") (pintype "passive"))
      (node (ref "TP12") (pin "1") (pintype "passive"))
    )
    (net (code "163") (name "/AWR_CONN_TP2") (class "Default")
      (node (ref "J4") (pin "52") (pinfunction "52_52") (pintype "passive"))
      (node (ref "TP15") (pin "1") (pintype "passive"))
    )
    (net (code "164") (name "/AWR_CONN_TP3") (class "Default")
      (node (ref "J5") (pin "69") (pinfunction "69_69") (pintype "passive"))
      (node (ref "TP8") (pin "1") (pintype "passive"))
    )
    (net (code "165") (name "/AWR_CONN_TP4") (class "Default")
      (node (ref "J5") (pin "99") (pinfunction "99_99") (pintype "passive"))
      (node (ref "TP13") (pin "1") (pintype "passive"))
    )
    (net (code "166") (name "/CONN_MONITOR_1") (class "Default")
      (node (ref "J4") (pin "1") (pinfunction "1_1") (pintype "passive"))
      (node (ref "J4") (pin "120") (pinfunction "120_120") (pintype "passive"))
      (node (ref "TP32") (pin "1") (pintype "passive"))
    )
    (net (code "167") (name "/CONN_MONITOR_2") (class "Default")
      (node (ref "J5") (pin "1") (pinfunction "1_1") (pintype "passive"))
      (node (ref "J5") (pin "120") (pinfunction "120_120") (pintype "passive"))
      (node (ref "TP33") (pin "1") (pintype "passive"))
    )
    (net (code "168") (name "/EXT_40MHZ_CLK_1V8") (class "Default")
      (node (ref "J4") (pin "74") (pinfunction "74_74") (pintype "passive"))
    )
    (net (code "169") (name "/EXT_DIG_SYNC") (class "Default")
      (node (ref "J4") (pin "64") (pinfunction "64_64") (pintype "passive"))
    )
    (net (code "170") (name "/GND_SENSE") (class "Default")
      (node (ref "J6") (pin "1") (pinfunction "1_1") (pintype "passive"))
      (node (ref "R20") (pin "2") (pinfunction "2_2") (pintype "passive"))
    )
    (net (code "171") (name "/NERROR_OUT") (class "Default")
      (node (ref "J4") (pin "75") (pinfunction "75_75") (pintype "passive"))
      (node (ref "R150") (pin "1") (pinfunction "1_1") (pintype "passive"))
      (node (ref "R154") (pin "2") (pinfunction "2_2") (pintype "passive"))
      (node (ref "R156") (pin "2") (pinfunction "2_2") (pintype "passive"))
      (node (ref "R158") (pin "2") (pinfunction "2_2") (pintype "passive"))
      (node (ref "R160") (pin "2") (pinfunction "2_2") (pintype "passive"))
    )
    (net (code "172") (name "/PMIC1_SCL") (class "Default")
      (node (ref "J4") (pin "72") (pinfunction "72_72") (pintype "passive"))
      (node (ref "R100") (pin "1") (pinfunction "1_1") (pintype "passive"))
      (node (ref "R102") (pin "1") (pinfunction "1_1") (pintype "passive"))
      (node (ref "R114") (pin "1") (pinfunction "1_1") (pintype "passive"))
      (node (ref "R98") (pin "1") (pinfunction "1_1") (pintype "passive"))
    )
    (net (code "173") (name "/PMIC1_SDA") (class "Default")
      (node (ref "J4") (pin "73") (pinfunction "73_73") (pintype "passive"))
      (node (ref "R101") (pin "1") (pinfunction "1_1") (pintype "passive"))
      (node (ref "R112") (pin "1") (pinfunction "1_1") (pintype "passive"))
      (node (ref "R125") (pin "1") (pinfunction "1_1") (pintype "passive"))
      (node (ref "R99") (pin "1") (pinfunction "1_1") (pintype "passive"))
    )
    (net (code "174") (name "/PMIC2_TMPSNS_SCL") (class "Default")
      (node (ref "J5") (pin "49") (pinfunction "49_49") (pintype "passive"))
    )
    (net (code "175") (name "/PMIC2_TMPSNS_SDA") (class "Default")
      (node (ref "J5") (pin "48") (pinfunction "48_48") (pintype "passive"))
    )
    (net (code "176") (name "/PMIC_BUCKEN") (class "Default")
      (node (ref "R145") (pin "1") (pinfunction "1_1") (pintype "passive"))
    )
    (net (code "177") (name "/PMIC_BUCKEN_CONN") (class "Default")
      (node (ref "J5") (pin "46") (pinfunction "46_46") (pintype "passive"))
      (node (ref "R145") (pin "2") (pinfunction "2_2") (pintype "passive"))
    )
    (net (code "178") (name "/PMIC_NRST") (class "Default")
      (node (ref "R146") (pin "1") (pinfunction "1_1") (pintype "passive"))
    )
    (net (code "179") (name "/PMIC_NRST_CONN") (class "Default")
      (node (ref "J5") (pin "47") (pinfunction "47_47") (pintype "passive"))
      (node (ref "R146") (pin "2") (pinfunction "2_2") (pintype "passive"))
    )
    (net (code "180") (name "/SYSTEM_5V0_SENSE") (class "Default")
      (node (ref "J6") (pin "4") (pinfunction "4_4") (pintype "passive"))
      (node (ref "R19") (pin "2") (pinfunction "2_2") (pintype "passive"))
    )
    (net (code "181") (name "/SYSTEM_PGOOD") (class "Default")
      (node (ref "J5") (pin "119") (pinfunction "119_119") (pintype "passive"))
    )
    (net (code "182") (name "/TMPSNS_ALERT") (class "Default")
      (node (ref "J5") (pin "57") (pinfunction "57_57") (pintype "passive"))
    )
    (net (code "183") (name "GND") (class "Default")
      (node (ref "C190") (pin "2") (pinfunction "-_2") (pintype "passive"))
      (node (ref "C191") (pin "2") (pinfunction "-_2") (pintype "passive"))
      (node (ref "C192") (pin "2") (pinfunction "-_2") (pintype "passive"))
      (node (ref "C193") (pin "2") (pinfunction "-_2") (pintype "passive"))
      (node (ref "C194") (pin "2") (pinfunction "-_2") (pintype "passive"))
      (node (ref "J4") (pin "10") (pinfunction "10_10") (pintype "passive"))
      (node (ref "J4") (pin "104") (pinfunction "104_104") (pintype "passive"))
      (node (ref "J4") (pin "108") (pinfunction "108_108") (pintype "passive"))
      (node (ref "J4") (pin "11") (pinfunction "11_11") (pintype "passive"))
      (node (ref "J4") (pin "111") (pinfunction "111_111") (pintype "passive"))
      (node (ref "J4") (pin "115") (pinfunction "115_115") (pintype "passive"))
      (node (ref "J4") (pin "14") (pinfunction "14_14") (pintype "passive"))
      (node (ref "J4") (pin "15") (pinfunction "15_15") (pintype "passive"))
      (node (ref "J4") (pin "18") (pinfunction "18_18") (pintype "passive"))
      (node (ref "J4") (pin "21") (pinfunction "21_21") (pintype "passive"))
      (node (ref "J4") (pin "23") (pinfunction "23_23") (pintype "passive"))
      (node (ref "J4") (pin "24") (pinfunction "24_24") (pintype "passive"))
      (node (ref "J4") (pin "27") (pinfunction "27_27") (pintype "passive"))
      (node (ref "J4") (pin "3") (pinfunction "3_3") (pintype "passive"))
      (node (ref "J4") (pin "30") (pinfunction "30_30") (pintype "passive"))
      (node (ref "J4") (pin "31") (pinfunction "31_31") (pintype "passive"))
      (node (ref "J4") (pin "32") (pinfunction "32_32") (pintype "passive"))
      (node (ref "J4") (pin "35") (pinfunction "35_35") (pintype "passive"))
      (node (ref "J4") (pin "36") (pinfunction "36_36") (pintype "passive"))
      (node (ref "J4") (pin "39") (pinfunction "39_39") (pintype "passive"))
      (node (ref "J4") (pin "40") (pinfunction "40_40") (pintype "passive"))
      (node (ref "J4") (pin "43") (pinfunction "43_43") (pintype "passive"))
      (node (ref "J4") (pin "44") (pinfunction "44_44") (pintype "passive"))
      (node (ref "J4") (pin "47") (pinfunction "47_47") (pintype "passive"))
      (node (ref "J4") (pin "48") (pinfunction "48_48") (pintype "passive"))
      (node (ref "J4") (pin "51") (pinfunction "51_51") (pintype "passive"))
      (node (ref "J4") (pin "53") (pinfunction "53_53") (pintype "passive"))
      (node (ref "J4") (pin "54") (pinfunction "54_54") (pintype "passive"))
      (node (ref "J4") (pin "57") (pinfunction "57_57") (pintype "passive"))
      (node (ref "J4") (pin "6") (pinfunction "6_6") (pintype "passive"))
      (node (ref "J4") (pin "60") (pinfunction "60_60") (pintype "passive"))
      (node (ref "J4") (pin "65") (pinfunction "65_65") (pintype "passive"))
      (node (ref "J4") (pin "7") (pinfunction "7_7") (pintype "passive"))
      (node (ref "J4") (pin "71") (pinfunction "71_71") (pintype "passive"))
      (node (ref "J4") (pin "76") (pinfunction "76_76") (pintype "passive"))
      (node (ref "J4") (pin "81") (pinfunction "81_81") (pintype "passive"))
      (node (ref "J4") (pin "87") (pinfunction "87_87") (pintype "passive"))
      (node (ref "J4") (pin "92") (pinfunction "92_92") (pintype "passive"))
      (node (ref "J4") (pin "95") (pinfunction "95_95") (pintype "passive"))
      (node (ref "J4") (pin "99") (pinfunction "99_99") (pintype "passive"))
      (node (ref "J4") (pin "MH1") (pinfunction "MH1_MH1") (pintype "passive"))
      (node (ref "J4") (pin "MH2") (pinfunction "MH2_MH2") (pintype "passive"))
      (node (ref "J4") (pin "P1") (pinfunction "P1_P1") (pintype "passive"))
      (node (ref "J4") (pin "P2") (pinfunction "P2_P2") (pintype "passive"))
      (node (ref "J5") (pin "10") (pinfunction "10_10") (pintype "passive"))
      (node (ref "J5") (pin "100") (pinfunction "100_100") (pintype "passive"))
      (node (ref "J5") (pin "103") (pinfunction "103_103") (pintype "passive"))
      (node (ref "J5") (pin "106") (pinfunction "106_106") (pintype "passive"))
      (node (ref "J5") (pin "107") (pinfunction "107_107") (pintype "passive"))
      (node (ref "J5") (pin "110") (pinfunction "110_110") (pintype "passive"))
      (node (ref "J5") (pin "111") (pinfunction "111_111") (pintype "passive"))
      (node (ref "J5") (pin "114") (pinfunction "114_114") (pintype "passive"))
      (node (ref "J5") (pin "115") (pinfunction "115_115") (pintype "passive"))
      (node (ref "J5") (pin "118") (pinfunction "118_118") (pintype "passive"))
      (node (ref "J5") (pin "13") (pinfunction "13_13") (pintype "passive"))
      (node (ref "J5") (pin "17") (pinfunction "17_17") (pintype "passive"))
      (node (ref "J5") (pin "22") (pinfunction "22_22") (pintype "passive"))
      (node (ref "J5") (pin "26") (pinfunction "26_26") (pintype "passive"))
      (node (ref "J5") (pin "29") (pinfunction "29_29") (pintype "passive"))
      (node (ref "J5") (pin "34") (pinfunction "34_34") (pintype "passive"))
      (node (ref "J5") (pin "40") (pinfunction "40_40") (pintype "passive"))
      (node (ref "J5") (pin "45") (pinfunction "45_45") (pintype "passive"))
      (node (ref "J5") (pin "50") (pinfunction "50_50") (pintype "passive"))
      (node (ref "J5") (pin "56") (pinfunction "56_56") (pintype "passive"))
      (node (ref "J5") (pin "6") (pinfunction "6_6") (pintype "passive"))
      (node (ref "J5") (pin "61") (pinfunction "61_61") (pintype "passive"))
      (node (ref "J5") (pin "64") (pinfunction "64_64") (pintype "passive"))
      (node (ref "J5") (pin "67") (pinfunction "67_67") (pintype "passive"))
      (node (ref "J5") (pin "68") (pinfunction "68_68") (pintype "passive"))
      (node (ref "J5") (pin "70") (pinfunction "70_70") (pintype "passive"))
      (node (ref "J5") (pin "73") (pinfunction "73_73") (pintype "passive"))
      (node (ref "J5") (pin "74") (pinfunction "74_74") (pintype "passive"))
      (node (ref "J5") (pin "77") (pinfunction "77_77") (pintype "passive"))
      (node (ref "J5") (pin "78") (pinfunction "78_78") (pintype "passive"))
      (node (ref "J5") (pin "81") (pinfunction "81_81") (pintype "passive"))
      (node (ref "J5") (pin "82") (pinfunction "82_82") (pintype "passive"))
      (node (ref "J5") (pin "85") (pinfunction "85_85") (pintype "passive"))
      (node (ref "J5") (pin "86") (pinfunction "86_86") (pintype "passive"))
      (node (ref "J5") (pin "89") (pinfunction "89_89") (pintype "passive"))
      (node (ref "J5") (pin "90") (pinfunction "90_90") (pintype "passive"))
      (node (ref "J5") (pin "91") (pinfunction "91_91") (pintype "passive"))
      (node (ref "J5") (pin "94") (pinfunction "94_94") (pintype "passive"))
      (node (ref "J5") (pin "97") (pinfunction "97_97") (pintype "passive"))
      (node (ref "J5") (pin "98") (pinfunction "98_98") (pintype "passive"))
      (node (ref "J5") (pin "MH1") (pinfunction "MH1_MH1") (pintype "passive"))
      (node (ref "J5") (pin "MH2") (pinfunction "MH2_MH2") (pintype "passive"))
      (node (ref "J5") (pin "P3") (pinfunction "P3_P3") (pintype "passive"))
      (node (ref "J5") (pin "P4") (pinfunction "P4_P4") (pintype "passive"))
      (node (ref "J6") (pin "2") (pinfunction "2_2") (pintype "passive"))
      (node (ref "J6") (pin "3") (pinfunction "3_3") (pintype "passive"))
      (node (ref "R20") (pin "1") (pinfunction "1_1") (pintype "passive"))
      (node (ref "TP16") (pin "1") (pintype "passive"))
      (node (ref "TP17") (pin "1") (pintype "passive"))
      (node (ref "TP18") (pin "1") (pintype "passive"))
      (node (ref "TP19") (pin "1") (pintype "passive"))
      (node (ref "TP20") (pin "1") (pintype "passive"))
      (node (ref "TP25") (pin "1") (pintype "passive"))
      (node (ref "TP29") (pin "1") (pintype "passive"))
      (node (ref "TP30") (pin "1") (pintype "passive"))
    )
    (net (code "184") (name "SYSTEM_3V3") (class "Default")
      (node (ref "R150") (pin "2") (pinfunction "2_2") (pintype "passive"))
    )
    (net (code "185") (name "SYSTEM_5V0") (class "Default")
      (node (ref "C190") (pin "1") (pinfunction "+_1") (pintype "passive"))
      (node (ref "C191") (pin "1") (pinfunction "+_1") (pintype "passive"))
      (node (ref "C192") (pin "1") (pinfunction "+_1") (pintype "passive"))
      (node (ref "C193") (pin "1") (pinfunction "+_1") (pintype "passive"))
      (node (ref "C194") (pin "1") (pinfunction "+_1") (pintype "passive"))
      (node (ref "J4") (pin "P3") (pinfunction "P3_P3") (pintype "passive"))
      (node (ref "J4") (pin "P4") (pinfunction "P4_P4") (pintype "passive"))
      (node (ref "J5") (pin "P1") (pinfunction "P1_P1") (pintype "passive"))
      (node (ref "J5") (pin "P2") (pinfunction "P2_P2") (pintype "passive"))
      (node (ref "J6") (pin "5") (pinfunction "5_5") (pintype "passive"))
      (node (ref "J6") (pin "6") (pinfunction "6_6") (pintype "passive"))
      (node (ref "R19") (pin "1") (pinfunction "1_1") (pintype "passive"))
    )
  )
)
